# LDR_ACC.net
KiCad netlist of a schematic drawn in EAGLE
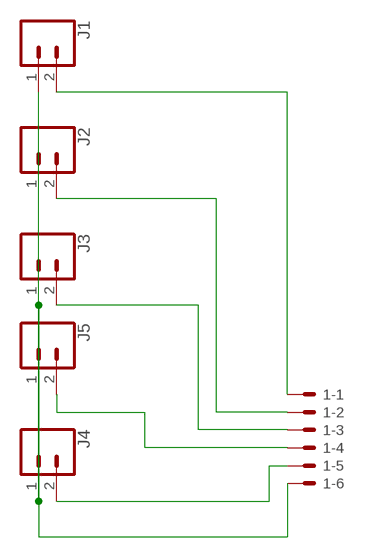
[diagram p0: schematic, sheet 1]

(export (version "E")
  (design (tool "Eeschema 10.0.6"))
  (components
    (comp (ref "1")
      (value "5566-6")
      (footprint "eagle-import:5566-6")
      (fields (field (name "MF") "MOLEX") (field (name "MPN") "95566-61002"))
      (libsource (lib "eagle-import") (part "5566-6"))
    )
    (comp (ref "J1")
      (value "CONN_02PTH3")
      (footprint "eagle-import:1X02_LONGPADS")
      (libsource (lib "eagle-import") (part "CONN_02PTH3"))
    )
    (comp (ref "J2")
      (value "CONN_02PTH3")
      (footprint "eagle-import:1X02_LONGPADS")
      (libsource (lib "eagle-import") (part "CONN_02PTH3"))
    )
    (comp (ref "J3")
      (value "CONN_02PTH3")
      (footprint "eagle-import:1X02_LONGPADS")
      (libsource (lib "eagle-import") (part "CONN_02PTH3"))
    )
    (comp (ref "J4")
      (value "CONN_02PTH3")
      (footprint "eagle-import:1X02_LONGPADS")
      (libsource (lib "eagle-import") (part "CONN_02PTH3"))
    )
    (comp (ref "J5")
      (value "CONN_02PTH3")
      (footprint "eagle-import:1X02_LONGPADS")
      (libsource (lib "eagle-import") (part "CONN_02PTH3"))
    )
  )
  (nets
    (net (code "1") (name "Net-(1A-S)") (class "Default")
      (node (ref "1") (pin "1") (pinfunction "S_1") (pintype "passive"))
      (node (ref "J1") (pin "2") (pinfunction "2_2") (pintype "passive"))
    )
    (net (code "2") (name "Net-(1B-S)") (class "Default")
      (node (ref "1") (pin "2") (pinfunction "S_2") (pintype "passive"))
      (node (ref "J2") (pin "2") (pinfunction "2_2") (pintype "passive"))
    )
    (net (code "3") (name "Net-(1C-S)") (class "Default")
      (node (ref "1") (pin "3") (pinfunction "S_3") (pintype "passive"))
      (node (ref "J3") (pin "2") (pinfunction "2_2") (pintype "passive"))
    )
    (net (code "4") (name "Net-(1D-S)") (class "Default")
      (node (ref "1") (pin "4") (pinfunction "S_4") (pintype "passive"))
      (node (ref "J5") (pin "2") (pinfunction "2_2") (pintype "passive"))
    )
    (net (code "5") (name "Net-(1E-S)") (class "Default")
      (node (ref "1") (pin "5") (pinfunction "S_5") (pintype "passive"))
      (node (ref "J4") (pin "2") (pinfunction "2_2") (pintype "passive"))
    )
    (net (code "6") (name "Net-(1F-S)") (class "Default")
      (node (ref "1") (pin "6") (pinfunction "S_6") (pintype "passive"))
      (node (ref "J1") (pin "1") (pinfunction "1_1") (pintype "passive"))
      (node (ref "J2") (pin "1") (pinfunction "1_1") (pintype "passive"))
      (node (ref "J3") (pin "1") (pinfunction "1_1") (pintype "passive"))
      (node (ref "J4") (pin "1") (pinfunction "1_1") (pintype "passive"))
      (node (ref "J5") (pin "1") (pinfunction "1_1") (pintype "passive"))
    )
  )
)
